# 2.net
KiCad netlist of a schematic drawn in Altium Designer
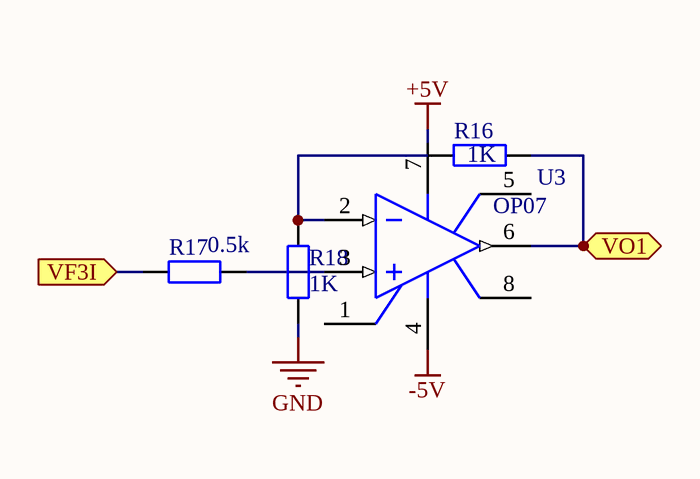
[diagram p0: 同向2倍放大.SchDoc]

(export (version "E")
  (design (tool "Eeschema 10.0.6"))
  (components
    (comp (ref "R16")
      (value "1K")
      (footprint "AXIAL-0.4")
      (description "Resistor")
      (fields (field (name "Comment") "Res2") (field (name "PUBLISHER") "Altium Limited"))
      (libsource (lib "Miscellaneous Devices") (part "Res2"))
    )
    (comp (ref "R17")
      (value "0.5k")
      (footprint "AXIAL-0.4")
      (description "Resistor")
      (fields (field (name "Comment") "Res2") (field (name "PUBLISHER") "Altium Limited"))
      (libsource (lib "Miscellaneous Devices") (part "Res2"))
    )
    (comp (ref "R18")
      (value "1K")
      (footprint "AXIAL-0.4")
      (description "Resistor")
      (fields (field (name "Comment") "Res2") (field (name "PUBLISHER") "Altium Limited"))
      (libsource (lib "") (part "Res2_1"))
    )
    (comp (ref "U3")
      (value "OP07")
      (footprint "N-8_A")
      (description "Ultra-Low Offset Voltage Operational Amplifier")
      (fields (field (name "PUBLISHER") "Altium Limited"))
      (libsource (lib "AD Operational Amplifier") (part "ADOP07CN"))
    )
  )
  (nets
    (net (code "1") (name "+5V") (class "Default")
      (node (ref "U3") (pin "7") (pinfunction "V+_7") (pintype "power_in"))
    )
    (net (code "2") (name "-5V") (class "Default")
      (node (ref "U3") (pin "4") (pinfunction "V-_4") (pintype "power_in"))
    )
    (net (code "3") (name "/VF3I") (class "Default")
      (node (ref "R17") (pin "1") (pinfunction "1_1") (pintype "passive"))
    )
    (net (code "4") (name "/VO1") (class "Default")
      (node (ref "R16") (pin "2") (pinfunction "2_2") (pintype "passive"))
      (node (ref "U3") (pin "6") (pinfunction "OUT_6") (pintype "output"))
    )
    (net (code "5") (name "GND") (class "Default")
      (node (ref "R18") (pin "1") (pinfunction "1_1") (pintype "passive"))
    )
    (net (code "6") (name "Net-(U3-IN+)") (class "Default")
      (node (ref "R17") (pin "2") (pinfunction "2_2") (pintype "passive"))
      (node (ref "U3") (pin "3") (pinfunction "IN+_3") (pintype "input"))
    )
    (net (code "7") (name "Net-(U3-IN-)") (class "Default")
      (node (ref "R16") (pin "1") (pinfunction "1_1") (pintype "passive"))
      (node (ref "R18") (pin "2") (pinfunction "2_2") (pintype "passive"))
      (node (ref "U3") (pin "2") (pinfunction "IN-_2") (pintype "input"))
    )
    (net (code "8") (name "unconnected-(U3-NC-Pad5)") (class "Default")
      (node (ref "U3") (pin "5") (pinfunction "NC_5") (pintype "passive"))
    )
    (net (code "9") (name "unconnected-(U3-NULL1-Pad1)") (class "Default")
      (node (ref "U3") (pin "1") (pinfunction "NULL1_1") (pintype "passive"))
    )
    (net (code "10") (name "unconnected-(U3-NULL2-Pad8)") (class "Default")
      (node (ref "U3") (pin "8") (pinfunction "NULL2_8") (pintype "passive"))
    )
  )
)
